# PIC_16F877A_Board_V3_SMD.net
KiCad netlist of a schematic drawn in EAGLE
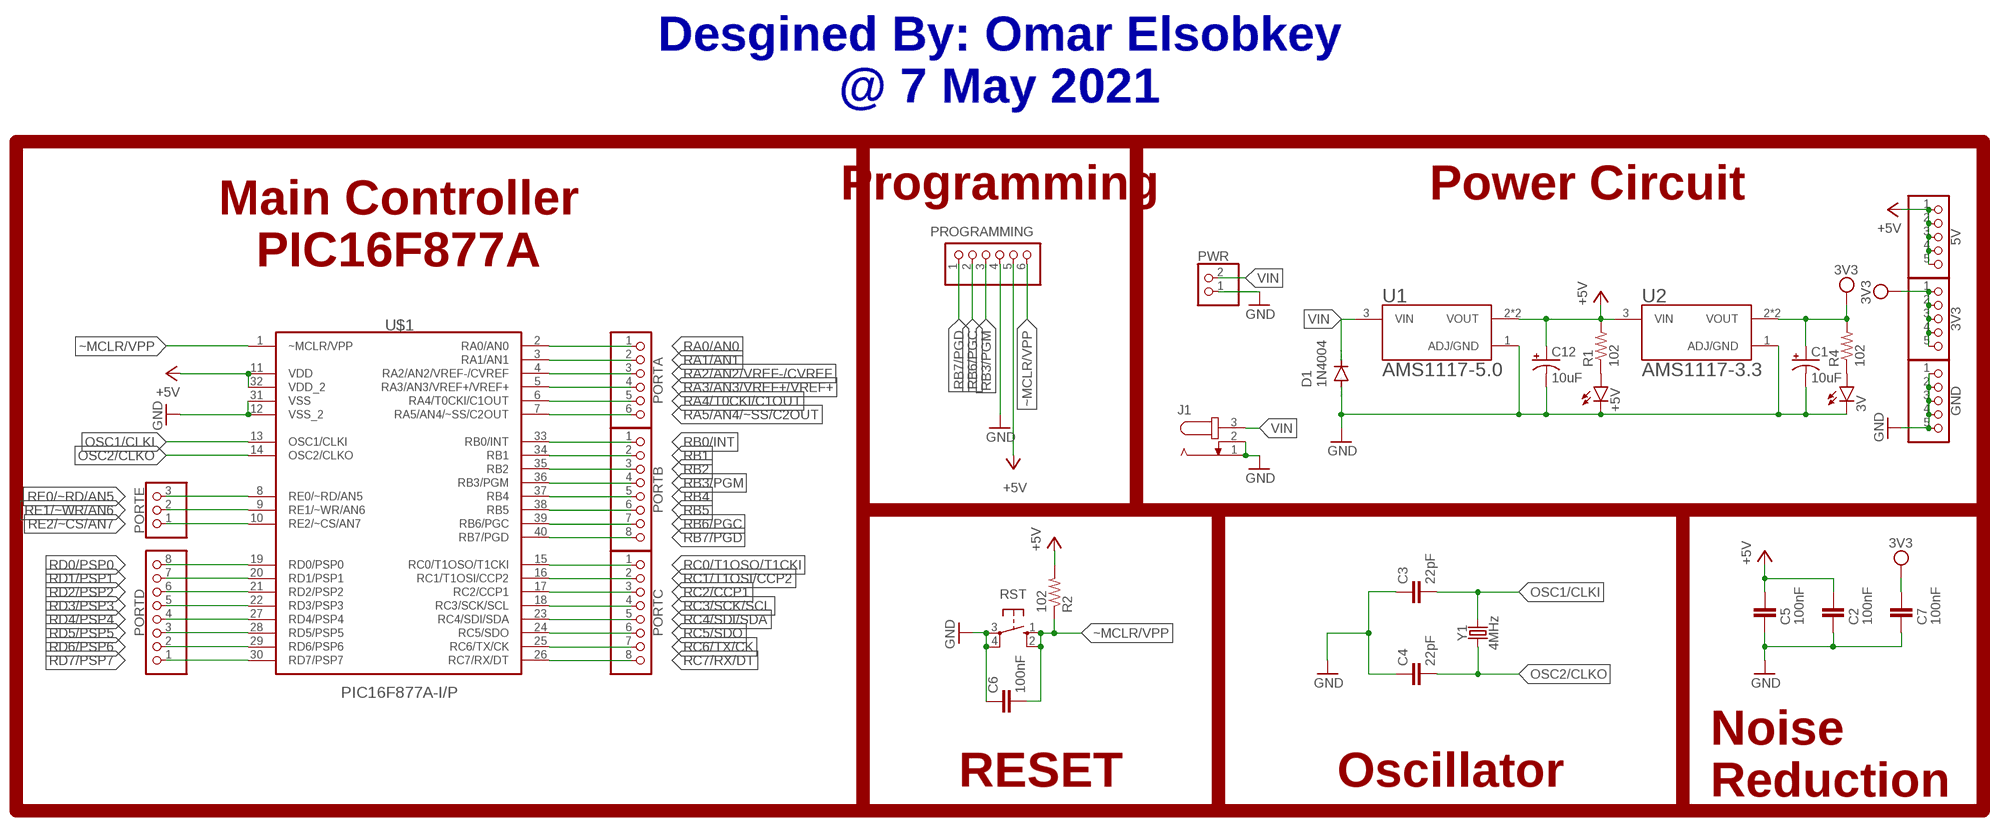
[diagram p0: schematic, sheet 1]

(export (version "E")
  (design (tool "Eeschema 10.0.6"))
  (components
    (comp (ref "+5V")
      (value "LEDSML0805")
      (footprint "eagle-import:SML0805")
      (libsource (lib "eagle-import") (part "LEDSML0805"))
    )
    (comp (ref "3V")
      (value "LEDSML0805")
      (footprint "eagle-import:SML0805")
      (libsource (lib "eagle-import") (part "LEDSML0805"))
    )
    (comp (ref "3V3")
      (value "PINHD-1X5")
      (footprint "eagle-import:1X05")
      (libsource (lib "eagle-import") (part "PINHD-1X5"))
    )
    (comp (ref "5V")
      (value "PINHD-1X5")
      (footprint "eagle-import:1X05")
      (libsource (lib "eagle-import") (part "PINHD-1X5"))
    )
    (comp (ref "C1")
      (value "10uF")
      (footprint "eagle-import:CPOL-RADIAL-2.5MM-5MM-KIT")
      (libsource (lib "eagle-import") (part "10UF-POLAR-RADIAL-2.5MM-KIT-25V-20%"))
    )
    (comp (ref "C2")
      (value "100nF")
      (footprint "eagle-import:C025-025X050")
      (libsource (lib "eagle-import") (part "C-EU025-025X050"))
    )
    (comp (ref "C3")
      (value "22pF")
      (footprint "eagle-import:C025-025X050")
      (libsource (lib "eagle-import") (part "C-EU025-025X050"))
    )
    (comp (ref "C4")
      (value "22pF")
      (footprint "eagle-import:C025-025X050")
      (libsource (lib "eagle-import") (part "C-EU025-025X050"))
    )
    (comp (ref "C5")
      (value "100nF")
      (footprint "eagle-import:C025-025X050")
      (libsource (lib "eagle-import") (part "C-EU025-025X050"))
    )
    (comp (ref "C6")
      (value "100nF")
      (footprint "eagle-import:C025-025X050")
      (libsource (lib "eagle-import") (part "C-EU025-025X050"))
    )
    (comp (ref "C7")
      (value "100nF")
      (footprint "eagle-import:C025-025X050")
      (libsource (lib "eagle-import") (part "C-EU025-025X050"))
    )
    (comp (ref "C12")
      (value "10uF")
      (footprint "eagle-import:CPOL-RADIAL-2.5MM-5MM-KIT")
      (libsource (lib "eagle-import") (part "10UF-POLAR-RADIAL-2.5MM-KIT-25V-20%"))
    )
    (comp (ref "D1")
      (value "1N4004")
      (footprint "eagle-import:DO41-10")
      (libsource (lib "eagle-import") (part "1N4004"))
    )
    (comp (ref "GND")
      (value "PINHD-1X5")
      (footprint "eagle-import:1X05")
      (libsource (lib "eagle-import") (part "PINHD-1X5"))
    )
    (comp (ref "J1")
      (value "JACK-PLUG0")
      (footprint "eagle-import:SPC4077")
      (libsource (lib "eagle-import") (part "JACK-PLUG0"))
    )
    (comp (ref "PORTA")
      (value "PINHD-1X6")
      (footprint "eagle-import:1X06")
      (libsource (lib "eagle-import") (part "PINHD-1X6"))
    )
    (comp (ref "PORTB")
      (value "PINHD-1X8")
      (footprint "eagle-import:1X08")
      (libsource (lib "eagle-import") (part "PINHD-1X8"))
    )
    (comp (ref "PORTC")
      (value "PINHD-1X8")
      (footprint "eagle-import:1X08")
      (libsource (lib "eagle-import") (part "PINHD-1X8"))
    )
    (comp (ref "PORTD")
      (value "PINHD-1X8")
      (footprint "eagle-import:1X08")
      (libsource (lib "eagle-import") (part "PINHD-1X8"))
    )
    (comp (ref "PORTE")
      (value "PINHD-1X3")
      (footprint "eagle-import:1X03")
      (libsource (lib "eagle-import") (part "PINHD-1X3"))
    )
    (comp (ref "PROGRAMMING")
      (value "PINHD-1X6")
      (footprint "eagle-import:1X06")
      (libsource (lib "eagle-import") (part "PINHD-1X6"))
    )
    (comp (ref "PWR")
      (value "PINHD-1X2")
      (footprint "eagle-import:1X02")
      (libsource (lib "eagle-import") (part "PINHD-1X2"))
    )
    (comp (ref "R1")
      (value "102")
      (footprint "eagle-import:1206")
      (libsource (lib "eagle-import") (part "RESISTOR1206"))
    )
    (comp (ref "R2")
      (value "102")
      (footprint "eagle-import:1206")
      (libsource (lib "eagle-import") (part "RESISTOR1206"))
    )
    (comp (ref "R4")
      (value "102")
      (footprint "eagle-import:1206")
      (libsource (lib "eagle-import") (part "RESISTOR1206"))
    )
    (comp (ref "RST")
      (value "10-XX")
      (footprint "eagle-import:B3F-10XX")
      (fields (field (name "MPN") "B3F-1000"))
      (libsource (lib "eagle-import") (part "10-XX"))
    )
    (comp (ref "U$1")
      (value "PIC16F877A-I/P")
      (footprint "eagle-import:16F877A")
      (fields (field (name "MF") "Microchip"))
      (libsource (lib "eagle-import") (part "PIC16F877A-I/P"))
    )
    (comp (ref "U1")
      (value "AMS1117-5.0")
      (footprint "eagle-import:AMS1117-5.0")
      (fields (field (name "MF") "Advanced Monolithic Systems"))
      (libsource (lib "eagle-import") (part "AMS1117-5.0"))
    )
    (comp (ref "U2")
      (value "AMS1117-3.3")
      (footprint "eagle-import:AMS1117-5.0")
      (fields (field (name "MF") "Advanced Monolithic Systems") (field (name "MP") "AMS1117-5.0"))
      (libsource (lib "eagle-import") (part "AMS1117-5.0"))
    )
    (comp (ref "Y1")
      (value "4MHz")
      (footprint "eagle-import:HC49U")
      (libsource (lib "eagle-import") (part "CRYSTALPTH-HC49UV"))
    )
  )
  (nets
    (net (code "1") (name "+5V") (class "Default")
      (node (ref "5V") (pin "1") (pinfunction "1_1") (pintype "passive"))
      (node (ref "5V") (pin "2") (pinfunction "2_2") (pintype "passive"))
      (node (ref "5V") (pin "3") (pinfunction "3_3") (pintype "passive"))
      (node (ref "5V") (pin "4") (pinfunction "4_4") (pintype "passive"))
      (node (ref "5V") (pin "5") (pinfunction "5_5") (pintype "passive"))
      (node (ref "C12") (pin "1") (pinfunction "+_1") (pintype "passive"))
      (node (ref "C2") (pin "2") (pinfunction "2_2") (pintype "passive"))
      (node (ref "C5") (pin "2") (pinfunction "2_2") (pintype "passive"))
      (node (ref "PROGRAMMING") (pin "5") (pinfunction "5_5") (pintype "passive"))
      (node (ref "R1") (pin "2") (pinfunction "2_2") (pintype "passive"))
      (node (ref "R2") (pin "2") (pinfunction "2_2") (pintype "passive"))
      (node (ref "U$1") (pin "11") (pinfunction "VDD_11") (pintype "power_in"))
      (node (ref "U$1") (pin "32") (pinfunction "VDD_2_32") (pintype "power_in"))
      (node (ref "U1") (pin "2") (pinfunction "VOUT_2") (pintype "output"))
      (node (ref "U1") (pin "4") (pinfunction "VOUT_4") (pintype "output"))
      (node (ref "U2") (pin "3") (pinfunction "VIN_3") (pintype "input"))
    )
    (net (code "2") (name "/RA5{slash}AN4{slash}~{SS{slash}C2OUT}") (class "Default")
      (node (ref "PORTA") (pin "6") (pinfunction "6_6") (pintype "passive"))
      (node (ref "U$1") (pin "7") (pinfunction "RA5/AN4/~{SS/C2OUT}_7") (pintype "bidirectional"))
    )
    (net (code "3") (name "/RE0{slash}~{RD{slash}AN5}") (class "Default")
      (node (ref "PORTE") (pin "3") (pinfunction "3_3") (pintype "passive"))
      (node (ref "U$1") (pin "8") (pinfunction "RE0/~{RD/AN5}_8") (pintype "bidirectional"))
    )
    (net (code "4") (name "/RE1{slash}~{WR{slash}AN6}") (class "Default")
      (node (ref "PORTE") (pin "2") (pinfunction "2_2") (pintype "passive"))
      (node (ref "U$1") (pin "9") (pinfunction "RE1/~{WR/AN6}_9") (pintype "bidirectional"))
    )
    (net (code "5") (name "/RE2{slash}~{CS{slash}AN7}") (class "Default")
      (node (ref "PORTE") (pin "1") (pinfunction "1_1") (pintype "passive"))
      (node (ref "U$1") (pin "10") (pinfunction "RE2/~{CS/AN7}_10") (pintype "bidirectional"))
    )
    (net (code "6") (name "/~{MCLR{slash}VPP}") (class "Default")
      (node (ref "C6") (pin "2") (pinfunction "2_2") (pintype "passive"))
      (node (ref "PROGRAMMING") (pin "6") (pinfunction "6_6") (pintype "passive"))
      (node (ref "R2") (pin "1") (pinfunction "1_1") (pintype "passive"))
      (node (ref "RST") (pin "1") (pinfunction "S_1") (pintype "passive"))
      (node (ref "RST") (pin "2") (pinfunction "S1_2") (pintype "passive"))
      (node (ref "U$1") (pin "1") (pinfunction "~{MCLR/VPP}_1") (pintype "input"))
    )
    (net (code "7") (name "3V3") (class "Default")
      (node (ref "3V3") (pin "1") (pinfunction "1_1") (pintype "passive"))
      (node (ref "3V3") (pin "2") (pinfunction "2_2") (pintype "passive"))
      (node (ref "3V3") (pin "3") (pinfunction "3_3") (pintype "passive"))
      (node (ref "3V3") (pin "4") (pinfunction "4_4") (pintype "passive"))
      (node (ref "3V3") (pin "5") (pinfunction "5_5") (pintype "passive"))
      (node (ref "C1") (pin "1") (pinfunction "+_1") (pintype "passive"))
      (node (ref "C7") (pin "2") (pinfunction "2_2") (pintype "passive"))
      (node (ref "R4") (pin "2") (pinfunction "2_2") (pintype "passive"))
      (node (ref "U2") (pin "2") (pinfunction "VOUT_2") (pintype "output"))
      (node (ref "U2") (pin "4") (pinfunction "VOUT_4") (pintype "output"))
    )
    (net (code "8") (name "GND") (class "Default")
      (node (ref "+5V") (pin "C") (pinfunction "C_C") (pintype "passive"))
      (node (ref "3V") (pin "C") (pinfunction "C_C") (pintype "passive"))
      (node (ref "C1") (pin "2") (pinfunction "-_2") (pintype "passive"))
      (node (ref "C12") (pin "2") (pinfunction "-_2") (pintype "passive"))
      (node (ref "C2") (pin "1") (pinfunction "1_1") (pintype "passive"))
      (node (ref "C3") (pin "1") (pinfunction "1_1") (pintype "passive"))
      (node (ref "C4") (pin "1") (pinfunction "1_1") (pintype "passive"))
      (node (ref "C5") (pin "1") (pinfunction "1_1") (pintype "passive"))
      (node (ref "C6") (pin "1") (pinfunction "1_1") (pintype "passive"))
      (node (ref "C7") (pin "1") (pinfunction "1_1") (pintype "passive"))
      (node (ref "D1") (pin "A") (pinfunction "A_A") (pintype "passive"))
      (node (ref "GND") (pin "1") (pinfunction "1_1") (pintype "passive"))
      (node (ref "GND") (pin "2") (pinfunction "2_2") (pintype "passive"))
      (node (ref "GND") (pin "3") (pinfunction "3_3") (pintype "passive"))
      (node (ref "GND") (pin "4") (pinfunction "4_4") (pintype "passive"))
      (node (ref "GND") (pin "5") (pinfunction "5_5") (pintype "passive"))
      (node (ref "J1") (pin "1") (pinfunction "1_1") (pintype "passive"))
      (node (ref "J1") (pin "2") (pinfunction "2_2") (pintype "passive"))
      (node (ref "PROGRAMMING") (pin "4") (pinfunction "4_4") (pintype "passive"))
      (node (ref "PWR") (pin "1") (pinfunction "1_1") (pintype "passive"))
      (node (ref "RST") (pin "3") (pinfunction "P_3") (pintype "passive"))
      (node (ref "RST") (pin "4") (pinfunction "P1_4") (pintype "passive"))
      (node (ref "U$1") (pin "12") (pinfunction "VSS_2_12") (pintype "power_in"))
      (node (ref "U$1") (pin "31") (pinfunction "VSS_31") (pintype "power_in"))
      (node (ref "U1") (pin "1") (pinfunction "ADJ/GND_1") (pintype "power_in"))
      (node (ref "U2") (pin "1") (pinfunction "ADJ/GND_1") (pintype "power_in"))
    )
    (net (code "9") (name "Net-(+5V-PadA)") (class "Default")
      (node (ref "+5V") (pin "A") (pinfunction "A_A") (pintype "passive"))
      (node (ref "R1") (pin "1") (pinfunction "1_1") (pintype "passive"))
    )
    (net (code "10") (name "Net-(3V-PadA)") (class "Default")
      (node (ref "3V") (pin "A") (pinfunction "A_A") (pintype "passive"))
      (node (ref "R4") (pin "1") (pinfunction "1_1") (pintype "passive"))
    )
    (net (code "11") (name "OSC1{slash}CLKI") (class "Default")
      (node (ref "C3") (pin "2") (pinfunction "2_2") (pintype "passive"))
      (node (ref "U$1") (pin "13") (pinfunction "OSC1/CLKI_13") (pintype "input"))
      (node (ref "Y1") (pin "2") (pinfunction "2_2") (pintype "passive"))
    )
    (net (code "12") (name "OSC2{slash}CLKO") (class "Default")
      (node (ref "C4") (pin "2") (pinfunction "2_2") (pintype "passive"))
      (node (ref "U$1") (pin "14") (pinfunction "OSC2/CLKO_14") (pintype "output"))
      (node (ref "Y1") (pin "1") (pinfunction "1_1") (pintype "passive"))
    )
    (net (code "13") (name "RA0{slash}AN0") (class "Default")
      (node (ref "PORTA") (pin "1") (pinfunction "1_1") (pintype "passive"))
      (node (ref "U$1") (pin "2") (pinfunction "RA0/AN0_2") (pintype "bidirectional"))
    )
    (net (code "14") (name "RA1{slash}AN1") (class "Default")
      (node (ref "PORTA") (pin "2") (pinfunction "2_2") (pintype "passive"))
      (node (ref "U$1") (pin "3") (pinfunction "RA1/AN1_3") (pintype "bidirectional"))
    )
    (net (code "15") (name "RA2{slash}AN2{slash}VREF-{slash}CVREF") (class "Default")
      (node (ref "PORTA") (pin "3") (pinfunction "3_3") (pintype "passive"))
      (node (ref "U$1") (pin "4") (pinfunction "RA2/AN2/VREF-/CVREF_4") (pintype "bidirectional"))
    )
    (net (code "16") (name "RA3{slash}AN3{slash}VREF+{slash}VREF+") (class "Default")
      (node (ref "PORTA") (pin "4") (pinfunction "4_4") (pintype "passive"))
      (node (ref "U$1") (pin "5") (pinfunction "RA3/AN3/VREF+/VREF+_5") (pintype "bidirectional"))
    )
    (net (code "17") (name "RA4{slash}T0CKI{slash}C1OUT") (class "Default")
      (node (ref "PORTA") (pin "5") (pinfunction "5_5") (pintype "passive"))
      (node (ref "U$1") (pin "6") (pinfunction "RA4/T0CKI/C1OUT_6") (pintype "bidirectional"))
    )
    (net (code "18") (name "RB0{slash}INT") (class "Default")
      (node (ref "PORTB") (pin "1") (pinfunction "1_1") (pintype "passive"))
      (node (ref "U$1") (pin "33") (pinfunction "RB0/INT_33") (pintype "bidirectional"))
    )
    (net (code "19") (name "RB1") (class "Default")
      (node (ref "PORTB") (pin "2") (pinfunction "2_2") (pintype "passive"))
      (node (ref "U$1") (pin "34") (pinfunction "RB1_34") (pintype "bidirectional"))
    )
    (net (code "20") (name "RB2") (class "Default")
      (node (ref "PORTB") (pin "3") (pinfunction "3_3") (pintype "passive"))
      (node (ref "U$1") (pin "35") (pinfunction "RB2_35") (pintype "bidirectional"))
    )
    (net (code "21") (name "RB3{slash}PGM") (class "Default")
      (node (ref "PORTB") (pin "4") (pinfunction "4_4") (pintype "passive"))
      (node (ref "PROGRAMMING") (pin "3") (pinfunction "3_3") (pintype "passive"))
      (node (ref "U$1") (pin "36") (pinfunction "RB3/PGM_36") (pintype "bidirectional"))
    )
    (net (code "22") (name "RB4") (class "Default")
      (node (ref "PORTB") (pin "5") (pinfunction "5_5") (pintype "passive"))
      (node (ref "U$1") (pin "37") (pinfunction "RB4_37") (pintype "bidirectional"))
    )
    (net (code "23") (name "RB5") (class "Default")
      (node (ref "PORTB") (pin "6") (pinfunction "6_6") (pintype "passive"))
      (node (ref "U$1") (pin "38") (pinfunction "RB5_38") (pintype "bidirectional"))
    )
    (net (code "24") (name "RB6{slash}PGC") (class "Default")
      (node (ref "PORTB") (pin "7") (pinfunction "7_7") (pintype "passive"))
      (node (ref "PROGRAMMING") (pin "2") (pinfunction "2_2") (pintype "passive"))
      (node (ref "U$1") (pin "39") (pinfunction "RB6/PGC_39") (pintype "bidirectional"))
    )
    (net (code "25") (name "RB7{slash}PGD") (class "Default")
      (node (ref "PORTB") (pin "8") (pinfunction "8_8") (pintype "passive"))
      (node (ref "PROGRAMMING") (pin "1") (pinfunction "1_1") (pintype "passive"))
      (node (ref "U$1") (pin "40") (pinfunction "RB7/PGD_40") (pintype "bidirectional"))
    )
    (net (code "26") (name "RC0{slash}T1OSO{slash}T1CKI") (class "Default")
      (node (ref "PORTC") (pin "1") (pinfunction "1_1") (pintype "passive"))
      (node (ref "U$1") (pin "15") (pinfunction "RC0/T1OSO/T1CKI_15") (pintype "bidirectional"))
    )
    (net (code "27") (name "RC1{slash}T1OSI{slash}CCP2") (class "Default")
      (node (ref "PORTC") (pin "2") (pinfunction "2_2") (pintype "passive"))
      (node (ref "U$1") (pin "16") (pinfunction "RC1/T1OSI/CCP2_16") (pintype "bidirectional"))
    )
    (net (code "28") (name "RC2{slash}CCP1") (class "Default")
      (node (ref "PORTC") (pin "3") (pinfunction "3_3") (pintype "passive"))
      (node (ref "U$1") (pin "17") (pinfunction "RC2/CCP1_17") (pintype "bidirectional"))
    )
    (net (code "29") (name "RC3{slash}SCK{slash}SCL") (class "Default")
      (node (ref "PORTC") (pin "4") (pinfunction "4_4") (pintype "passive"))
      (node (ref "U$1") (pin "18") (pinfunction "RC3/SCK/SCL_18") (pintype "bidirectional"))
    )
    (net (code "30") (name "RC4{slash}SDI{slash}SDA") (class "Default")
      (node (ref "PORTC") (pin "5") (pinfunction "5_5") (pintype "passive"))
      (node (ref "U$1") (pin "23") (pinfunction "RC4/SDI/SDA_23") (pintype "bidirectional"))
    )
    (net (code "31") (name "RC5{slash}SDO") (class "Default")
      (node (ref "PORTC") (pin "6") (pinfunction "6_6") (pintype "passive"))
      (node (ref "U$1") (pin "24") (pinfunction "RC5/SDO_24") (pintype "bidirectional"))
    )
    (net (code "32") (name "RC6{slash}TX{slash}CK") (class "Default")
      (node (ref "PORTC") (pin "7") (pinfunction "7_7") (pintype "passive"))
      (node (ref "U$1") (pin "25") (pinfunction "RC6/TX/CK_25") (pintype "bidirectional"))
    )
    (net (code "33") (name "RC7{slash}RX{slash}DT") (class "Default")
      (node (ref "PORTC") (pin "8") (pinfunction "8_8") (pintype "passive"))
      (node (ref "U$1") (pin "26") (pinfunction "RC7/RX/DT_26") (pintype "bidirectional"))
    )
    (net (code "34") (name "RD0{slash}PSP0") (class "Default")
      (node (ref "PORTD") (pin "8") (pinfunction "8_8") (pintype "passive"))
      (node (ref "U$1") (pin "19") (pinfunction "RD0/PSP0_19") (pintype "bidirectional"))
    )
    (net (code "35") (name "RD1{slash}PSP1") (class "Default")
      (node (ref "PORTD") (pin "7") (pinfunction "7_7") (pintype "passive"))
      (node (ref "U$1") (pin "20") (pinfunction "RD1/PSP1_20") (pintype "bidirectional"))
    )
    (net (code "36") (name "RD2{slash}PSP2") (class "Default")
      (node (ref "PORTD") (pin "6") (pinfunction "6_6") (pintype "passive"))
      (node (ref "U$1") (pin "21") (pinfunction "RD2/PSP2_21") (pintype "bidirectional"))
    )
    (net (code "37") (name "RD3{slash}PSP3") (class "Default")
      (node (ref "PORTD") (pin "5") (pinfunction "5_5") (pintype "passive"))
      (node (ref "U$1") (pin "22") (pinfunction "RD3/PSP3_22") (pintype "bidirectional"))
    )
    (net (code "38") (name "RD4{slash}PSP4") (class "Default")
      (node (ref "PORTD") (pin "4") (pinfunction "4_4") (pintype "passive"))
      (node (ref "U$1") (pin "27") (pinfunction "RD4/PSP4_27") (pintype "bidirectional"))
    )
    (net (code "39") (name "RD5{slash}PSP5") (class "Default")
      (node (ref "PORTD") (pin "3") (pinfunction "3_3") (pintype "passive"))
      (node (ref "U$1") (pin "28") (pinfunction "RD5/PSP5_28") (pintype "bidirectional"))
    )
    (net (code "40") (name "RD6{slash}PSP6") (class "Default")
      (node (ref "PORTD") (pin "2") (pinfunction "2_2") (pintype "passive"))
      (node (ref "U$1") (pin "29") (pinfunction "RD6/PSP6_29") (pintype "bidirectional"))
    )
    (net (code "41") (name "RD7{slash}PSP7") (class "Default")
      (node (ref "PORTD") (pin "1") (pinfunction "1_1") (pintype "passive"))
      (node (ref "U$1") (pin "30") (pinfunction "RD7/PSP7_30") (pintype "bidirectional"))
    )
    (net (code "42") (name "VIN") (class "Default")
      (node (ref "D1") (pin "C") (pinfunction "C_C") (pintype "passive"))
      (node (ref "J1") (pin "3") (pinfunction "3_3") (pintype "passive"))
      (node (ref "PWR") (pin "2") (pinfunction "2_2") (pintype "passive"))
      (node (ref "U1") (pin "3") (pinfunction "VIN_3") (pintype "input"))
    )
  )
)
